# SoM.net
KiCad netlist of a schematic drawn in Altium Designer
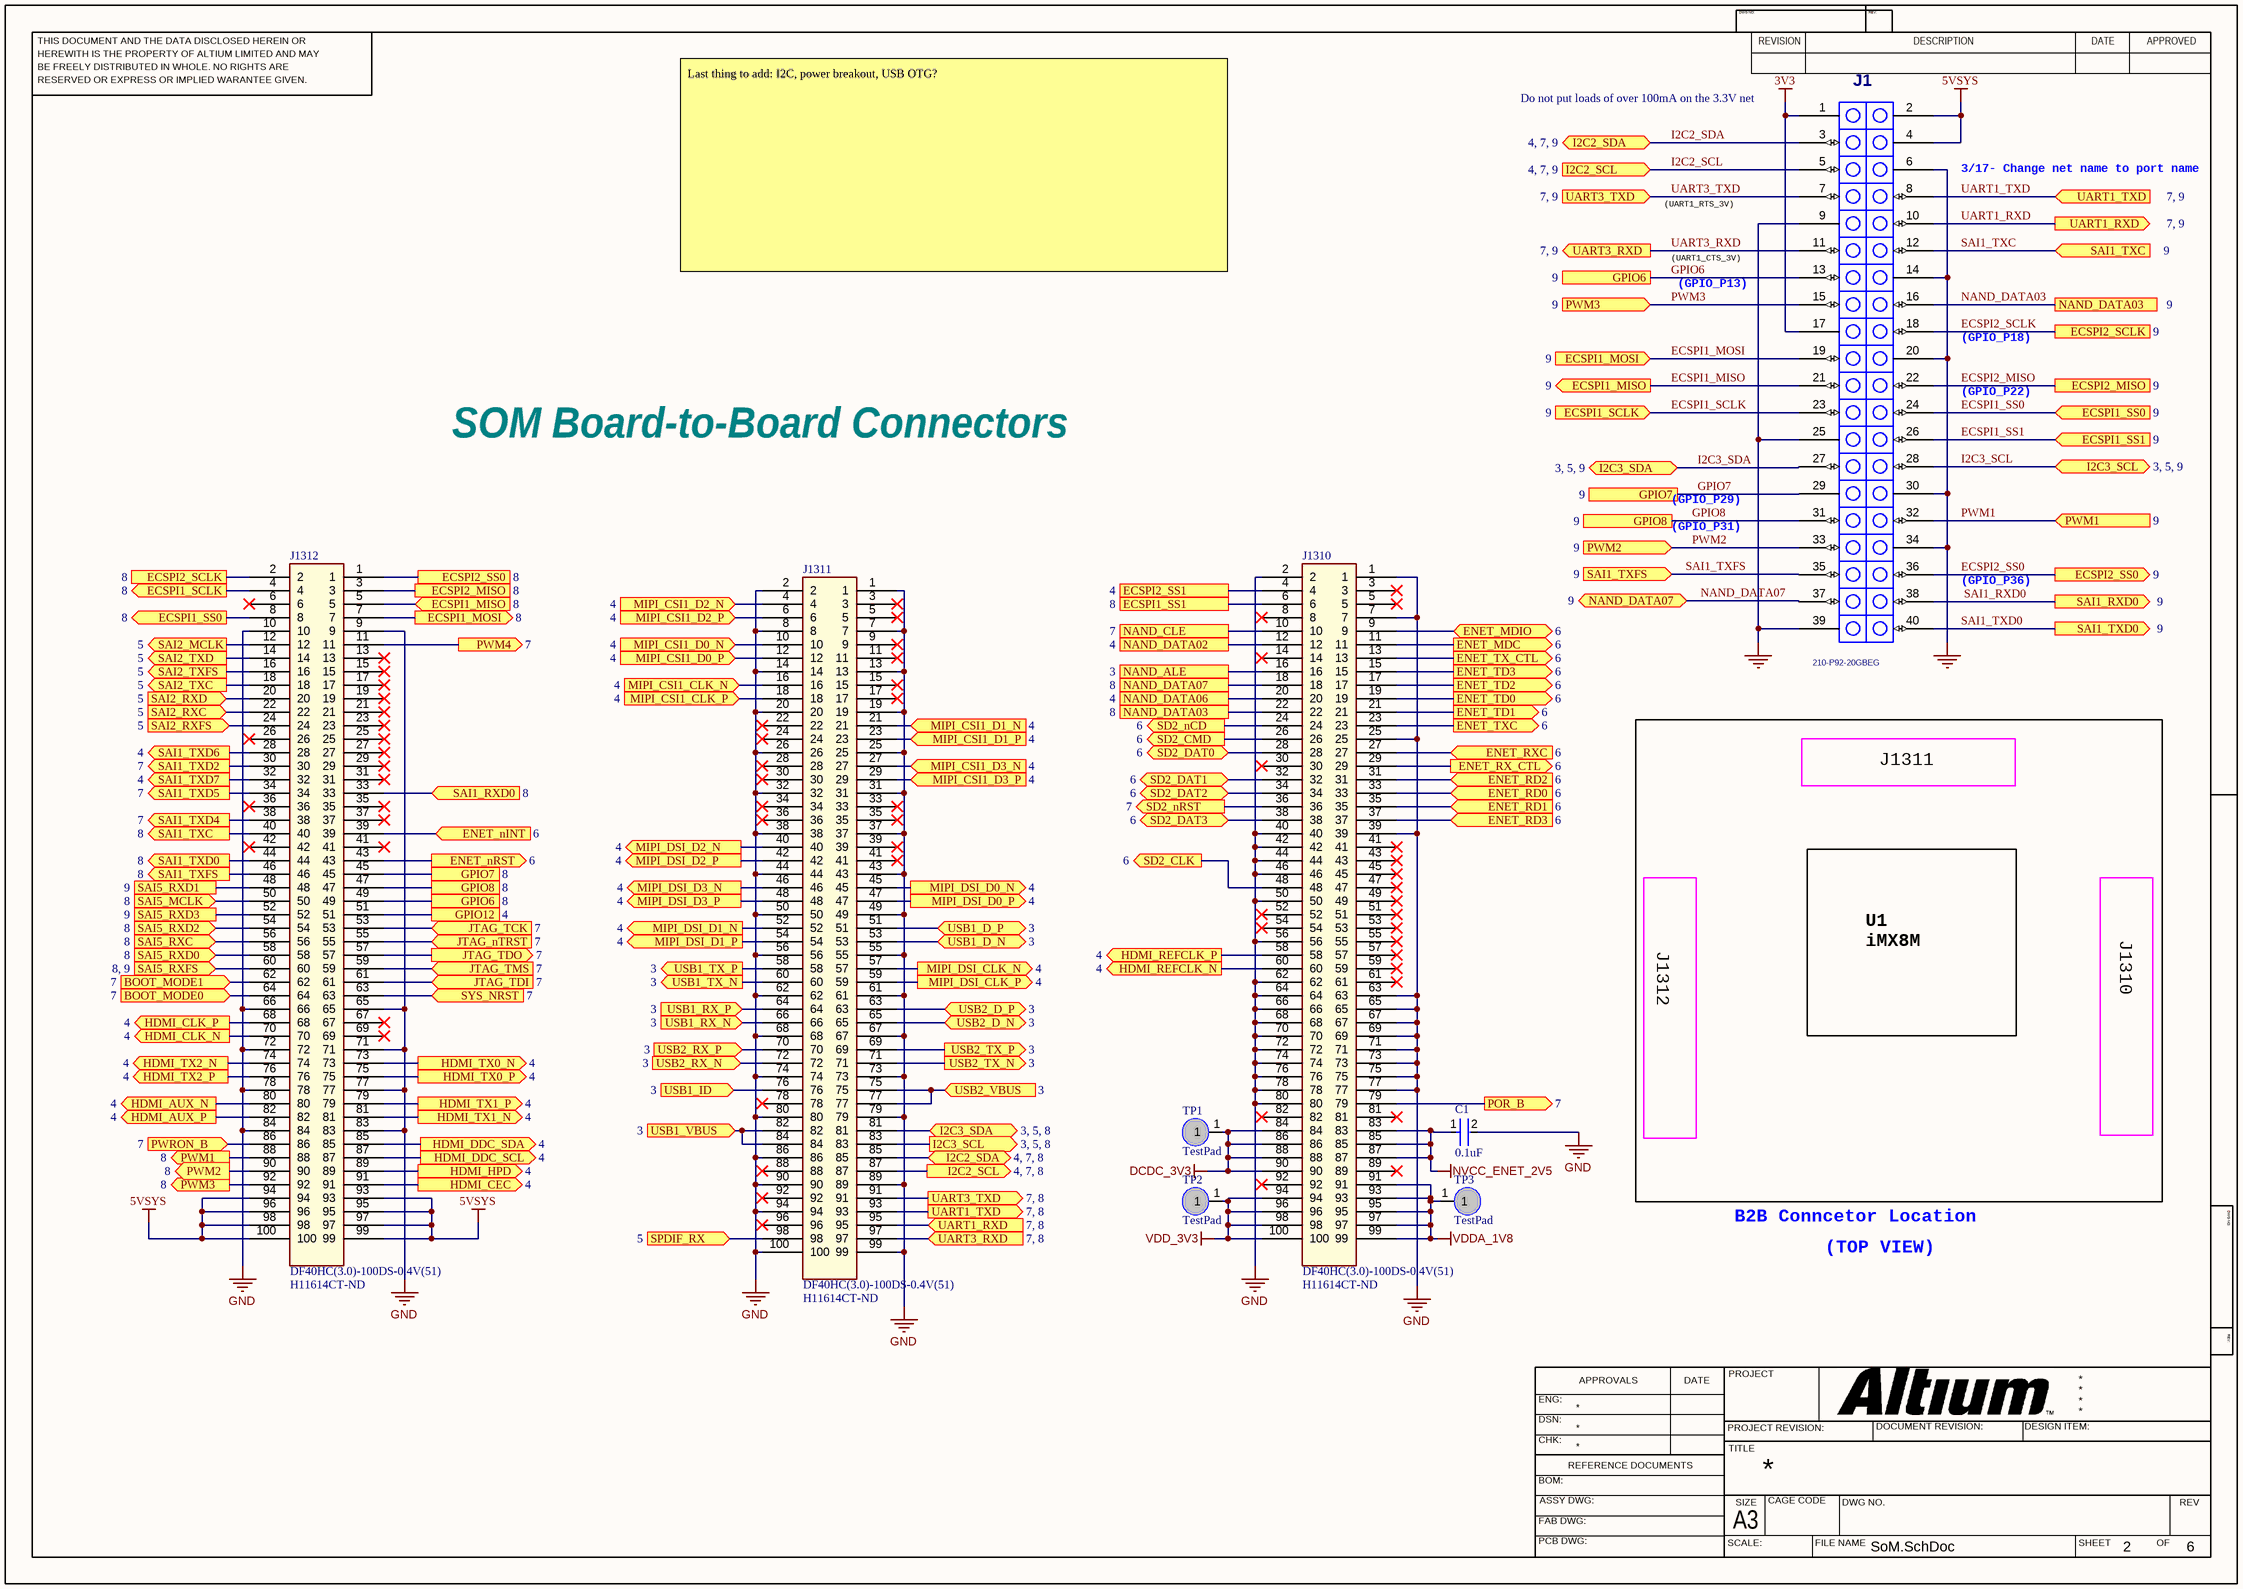
[diagram p0: SoM.SchDoc]

(export (version "E")
  (design (tool "Eeschema 10.0.6"))
  (components
    (comp (ref "C1")
      (value "0.1uF")
      (footprint "FP-C0603-CJ-MFG")
      (description "C0603X104K5RACTU CAP CER 0.1UF 50V X7R 0603")
      (fields (field (name "MANUFACTURER PART NUMBER") "C0603X104K5RACTU") (field (name "VOLTAGE") "50V"))
      (libsource (lib "Altium Content Vault") (part "11868f565c42a9108669ba33697ecf6"))
    )
    (comp (ref "J1")
      (value "210-P92-20GBEG")
      (footprint "LayoutFootprintsGoogle:2X20")
      (description "SOCKET 2X20 100-MIL STRAIGHT SMT")
      (libsource (lib "SpacePark") (part "CONN_HEADER_20x2_SMT"))
    )
    (comp (ref "J1310")
      (value "DF40HC(3.0)-100DS-0.4V(51)")
      (footprint "LayoutFootprintsGoogle:DF40HC30100DS04V51")
      (description "CONN HDR 100POS 0.4MM SMD GOLD")
      (fields (field (name "SUPPLIER PART NUMBER 1") "H11614CT-ND"))
      (libsource (lib "SpacePark") (part "CONN_HIROSE-DF40C-100DP-0.4V(51)"))
    )
    (comp (ref "J1311")
      (value "DF40HC(3.0)-100DS-0.4V(51)")
      (footprint "LayoutFootprintsGoogle:DF40HC30100DS04V51")
      (description "CONN HDR 100POS 0.4MM SMD GOLD")
      (fields (field (name "SUPPLIER PART NUMBER 1") "H11614CT-ND"))
      (libsource (lib "SpacePark") (part "CONN_HIROSE-DF40C-100DP-0.4V(51)"))
    )
    (comp (ref "J1312")
      (value "DF40HC(3.0)-100DS-0.4V(51)")
      (footprint "LayoutFootprintsGoogle:DF40HC30100DS04V51")
      (description "CONN HDR 100POS 0.4MM SMD GOLD")
      (fields (field (name "SUPPLIER PART NUMBER 1") "H11614CT-ND"))
      (libsource (lib "SpacePark") (part "CONN_HIROSE-DF40C-100DP-0.4V(51)"))
    )
    (comp (ref "TP1")
      (value "TestPad")
      (footprint "TestPad50mil")
      (libsource (lib "SchemSymbolsGoogle") (part "TestPad"))
    )
    (comp (ref "TP2")
      (value "TestPad")
      (footprint "TestPad50mil")
      (libsource (lib "SchemSymbolsGoogle") (part "TestPad"))
    )
    (comp (ref "TP3")
      (value "TestPad")
      (footprint "TestPad50mil")
      (libsource (lib "SchemSymbolsGoogle") (part "TestPad"))
    )
  )
  (nets
    (net (code "1") (name "/BOOT_MODE0") (class "Default")
      (node (ref "J1312") (pin "64") (pinfunction "64_64") (pintype "passive"))
    )
    (net (code "2") (name "/BOOT_MODE1") (class "Default")
      (node (ref "J1312") (pin "62") (pinfunction "62_62") (pintype "passive"))
    )
    (net (code "3") (name "/ECSPI1_MISO") (class "Default")
      (node (ref "J1") (pin "21") (pinfunction "21_21") (pintype "bidirectional"))
      (node (ref "J1312") (pin "5") (pinfunction "5_5") (pintype "passive"))
    )
    (net (code "4") (name "/ECSPI1_MOSI") (class "Default")
      (node (ref "J1") (pin "19") (pinfunction "19_19") (pintype "bidirectional"))
      (node (ref "J1312") (pin "7") (pinfunction "7_7") (pintype "passive"))
    )
    (net (code "5") (name "/ECSPI1_SCLK") (class "Default")
      (node (ref "J1") (pin "23") (pinfunction "23_23") (pintype "bidirectional"))
      (node (ref "J1312") (pin "4") (pinfunction "4_4") (pintype "passive"))
    )
    (net (code "6") (name "/ECSPI1_SS0") (class "Default")
      (node (ref "J1") (pin "24") (pinfunction "24_24") (pintype "bidirectional"))
      (node (ref "J1312") (pin "8") (pinfunction "8_8") (pintype "passive"))
    )
    (net (code "7") (name "/ECSPI1_SS1") (class "Default")
      (node (ref "J1") (pin "26") (pinfunction "26_26") (pintype "bidirectional"))
      (node (ref "J1310") (pin "6") (pinfunction "6_6") (pintype "passive"))
    )
    (net (code "8") (name "/ECSPI2_MISO") (class "Default")
      (node (ref "J1") (pin "22") (pinfunction "22_22") (pintype "bidirectional"))
      (node (ref "J1312") (pin "3") (pinfunction "3_3") (pintype "passive"))
    )
    (net (code "9") (name "/ECSPI2_SCLK") (class "Default")
      (node (ref "J1") (pin "18") (pinfunction "18_18") (pintype "bidirectional"))
      (node (ref "J1312") (pin "2") (pinfunction "2_2") (pintype "passive"))
    )
    (net (code "10") (name "/ECSPI2_SS0") (class "Default")
      (node (ref "J1") (pin "36") (pinfunction "36_36") (pintype "bidirectional"))
      (node (ref "J1312") (pin "1") (pinfunction "1_1") (pintype "passive"))
    )
    (net (code "11") (name "/ECSPI2_SS1") (class "Default")
      (node (ref "J1310") (pin "4") (pinfunction "4_4") (pintype "passive"))
    )
    (net (code "12") (name "/ENET_MDC") (class "Default")
      (node (ref "J1310") (pin "11") (pinfunction "11_11") (pintype "passive"))
    )
    (net (code "13") (name "/ENET_MDIO") (class "Default")
      (node (ref "J1310") (pin "9") (pinfunction "9_9") (pintype "passive"))
    )
    (net (code "14") (name "/ENET_RD0") (class "Default")
      (node (ref "J1310") (pin "33") (pinfunction "33_33") (pintype "passive"))
    )
    (net (code "15") (name "/ENET_RD1") (class "Default")
      (node (ref "J1310") (pin "35") (pinfunction "35_35") (pintype "passive"))
    )
    (net (code "16") (name "/ENET_RD2") (class "Default")
      (node (ref "J1310") (pin "31") (pinfunction "31_31") (pintype "passive"))
    )
    (net (code "17") (name "/ENET_RD3") (class "Default")
      (node (ref "J1310") (pin "37") (pinfunction "37_37") (pintype "passive"))
    )
    (net (code "18") (name "/ENET_RXC") (class "Default")
      (node (ref "J1310") (pin "27") (pinfunction "27_27") (pintype "passive"))
    )
    (net (code "19") (name "/ENET_RX_CTL") (class "Default")
      (node (ref "J1310") (pin "29") (pinfunction "29_29") (pintype "passive"))
    )
    (net (code "20") (name "/ENET_TD0") (class "Default")
      (node (ref "J1310") (pin "19") (pinfunction "19_19") (pintype "passive"))
    )
    (net (code "21") (name "/ENET_TD1") (class "Default")
      (node (ref "J1310") (pin "21") (pinfunction "21_21") (pintype "passive"))
    )
    (net (code "22") (name "/ENET_TD2") (class "Default")
      (node (ref "J1310") (pin "17") (pinfunction "17_17") (pintype "passive"))
    )
    (net (code "23") (name "/ENET_TD3") (class "Default")
      (node (ref "J1310") (pin "15") (pinfunction "15_15") (pintype "passive"))
    )
    (net (code "24") (name "/ENET_TXC") (class "Default")
      (node (ref "J1310") (pin "23") (pinfunction "23_23") (pintype "passive"))
    )
    (net (code "25") (name "/ENET_TX_CTL") (class "Default")
      (node (ref "J1310") (pin "13") (pinfunction "13_13") (pintype "passive"))
    )
    (net (code "26") (name "/ENET_nINT") (class "Default")
      (node (ref "J1312") (pin "39") (pinfunction "39_39") (pintype "passive"))
    )
    (net (code "27") (name "/ENET_nRST") (class "Default")
      (node (ref "J1312") (pin "43") (pinfunction "43_43") (pintype "passive"))
    )
    (net (code "28") (name "/GPIO6") (class "Default")
      (node (ref "J1") (pin "13") (pinfunction "13_13") (pintype "bidirectional"))
      (node (ref "J1312") (pin "49") (pinfunction "49_49") (pintype "passive"))
    )
    (net (code "29") (name "/GPIO7") (class "Default")
      (node (ref "J1") (pin "29") (pinfunction "29_29") (pintype "passive"))
      (node (ref "J1312") (pin "45") (pinfunction "45_45") (pintype "passive"))
    )
    (net (code "30") (name "/GPIO8") (class "Default")
      (node (ref "J1") (pin "31") (pinfunction "31_31") (pintype "bidirectional"))
      (node (ref "J1312") (pin "47") (pinfunction "47_47") (pintype "passive"))
    )
    (net (code "31") (name "/GPIO12") (class "Default")
      (node (ref "J1312") (pin "51") (pinfunction "51_51") (pintype "passive"))
    )
    (net (code "32") (name "/HDMI_AUX_N") (class "Default")
      (node (ref "J1312") (pin "80") (pinfunction "80_80") (pintype "passive"))
    )
    (net (code "33") (name "/HDMI_AUX_P") (class "Default")
      (node (ref "J1312") (pin "82") (pinfunction "82_82") (pintype "passive"))
    )
    (net (code "34") (name "/HDMI_CEC") (class "Default")
      (node (ref "J1312") (pin "91") (pinfunction "91_91") (pintype "passive"))
    )
    (net (code "35") (name "/HDMI_CLK_N") (class "Default")
      (node (ref "J1312") (pin "70") (pinfunction "70_70") (pintype "passive"))
    )
    (net (code "36") (name "/HDMI_CLK_P") (class "Default")
      (node (ref "J1312") (pin "68") (pinfunction "68_68") (pintype "passive"))
    )
    (net (code "37") (name "/HDMI_DDC_SCL") (class "Default")
      (node (ref "J1312") (pin "87") (pinfunction "87_87") (pintype "passive"))
    )
    (net (code "38") (name "/HDMI_DDC_SDA") (class "Default")
      (node (ref "J1312") (pin "85") (pinfunction "85_85") (pintype "passive"))
    )
    (net (code "39") (name "/HDMI_HPD") (class "Default")
      (node (ref "J1312") (pin "89") (pinfunction "89_89") (pintype "passive"))
    )
    (net (code "40") (name "/HDMI_REFCLK_N") (class "Default")
      (node (ref "J1310") (pin "60") (pinfunction "60_60") (pintype "passive"))
    )
    (net (code "41") (name "/HDMI_REFCLK_P") (class "Default")
      (node (ref "J1310") (pin "58") (pinfunction "58_58") (pintype "passive"))
    )
    (net (code "42") (name "/HDMI_TX0_N") (class "Default")
      (node (ref "J1312") (pin "73") (pinfunction "73_73") (pintype "passive"))
    )
    (net (code "43") (name "/HDMI_TX0_P") (class "Default")
      (node (ref "J1312") (pin "75") (pinfunction "75_75") (pintype "passive"))
    )
    (net (code "44") (name "/HDMI_TX1_N") (class "Default")
      (node (ref "J1312") (pin "81") (pinfunction "81_81") (pintype "passive"))
    )
    (net (code "45") (name "/HDMI_TX1_P") (class "Default")
      (node (ref "J1312") (pin "79") (pinfunction "79_79") (pintype "passive"))
    )
    (net (code "46") (name "/HDMI_TX2_N") (class "Default")
      (node (ref "J1312") (pin "74") (pinfunction "74_74") (pintype "passive"))
    )
    (net (code "47") (name "/HDMI_TX2_P") (class "Default")
      (node (ref "J1312") (pin "76") (pinfunction "76_76") (pintype "passive"))
    )
    (net (code "48") (name "/I2C2_SCL") (class "Default")
      (node (ref "J1") (pin "5") (pinfunction "5_5") (pintype "bidirectional"))
      (node (ref "J1311") (pin "87") (pinfunction "87_87") (pintype "passive"))
    )
    (net (code "49") (name "/I2C2_SDA") (class "Default")
      (node (ref "J1") (pin "3") (pinfunction "3_3") (pintype "bidirectional"))
      (node (ref "J1311") (pin "85") (pinfunction "85_85") (pintype "passive"))
    )
    (net (code "50") (name "/I2C3_SCL") (class "Default")
      (node (ref "J1") (pin "28") (pinfunction "28_28") (pintype "bidirectional"))
      (node (ref "J1311") (pin "83") (pinfunction "83_83") (pintype "passive"))
    )
    (net (code "51") (name "/I2C3_SDA") (class "Default")
      (node (ref "J1") (pin "27") (pinfunction "27_27") (pintype "bidirectional"))
      (node (ref "J1311") (pin "81") (pinfunction "81_81") (pintype "passive"))
    )
    (net (code "52") (name "/JTAG_TCK") (class "Default")
      (node (ref "J1312") (pin "53") (pinfunction "53_53") (pintype "passive"))
    )
    (net (code "53") (name "/JTAG_TDI") (class "Default")
      (node (ref "J1312") (pin "61") (pinfunction "61_61") (pintype "passive"))
    )
    (net (code "54") (name "/JTAG_TDO") (class "Default")
      (node (ref "J1312") (pin "57") (pinfunction "57_57") (pintype "passive"))
    )
    (net (code "55") (name "/JTAG_TMS") (class "Default")
      (node (ref "J1312") (pin "59") (pinfunction "59_59") (pintype "passive"))
    )
    (net (code "56") (name "/JTAG_nTRST") (class "Default")
      (node (ref "J1312") (pin "55") (pinfunction "55_55") (pintype "passive"))
    )
    (net (code "57") (name "/MIPI_CSI1_CLK_N") (class "Default")
      (node (ref "J1311") (pin "16") (pinfunction "16_16") (pintype "passive"))
    )
    (net (code "58") (name "/MIPI_CSI1_CLK_P") (class "Default")
      (node (ref "J1311") (pin "18") (pinfunction "18_18") (pintype "passive"))
    )
    (net (code "59") (name "/MIPI_CSI1_D0_N") (class "Default")
      (node (ref "J1311") (pin "10") (pinfunction "10_10") (pintype "passive"))
    )
    (net (code "60") (name "/MIPI_CSI1_D0_P") (class "Default")
      (node (ref "J1311") (pin "12") (pinfunction "12_12") (pintype "passive"))
    )
    (net (code "61") (name "/MIPI_CSI1_D1_N") (class "Default")
      (node (ref "J1311") (pin "21") (pinfunction "21_21") (pintype "passive"))
    )
    (net (code "62") (name "/MIPI_CSI1_D1_P") (class "Default")
      (node (ref "J1311") (pin "23") (pinfunction "23_23") (pintype "passive"))
    )
    (net (code "63") (name "/MIPI_CSI1_D2_N") (class "Default")
      (node (ref "J1311") (pin "4") (pinfunction "4_4") (pintype "passive"))
    )
    (net (code "64") (name "/MIPI_CSI1_D2_P") (class "Default")
      (node (ref "J1311") (pin "6") (pinfunction "6_6") (pintype "passive"))
    )
    (net (code "65") (name "/MIPI_CSI1_D3_N") (class "Default")
      (node (ref "J1311") (pin "27") (pinfunction "27_27") (pintype "passive"))
    )
    (net (code "66") (name "/MIPI_CSI1_D3_P") (class "Default")
      (node (ref "J1311") (pin "29") (pinfunction "29_29") (pintype "passive"))
    )
    (net (code "67") (name "/MIPI_DSI_CLK_N") (class "Default")
      (node (ref "J1311") (pin "57") (pinfunction "57_57") (pintype "passive"))
    )
    (net (code "68") (name "/MIPI_DSI_CLK_P") (class "Default")
      (node (ref "J1311") (pin "59") (pinfunction "59_59") (pintype "passive"))
    )
    (net (code "69") (name "/MIPI_DSI_D0_N") (class "Default")
      (node (ref "J1311") (pin "45") (pinfunction "45_45") (pintype "passive"))
    )
    (net (code "70") (name "/MIPI_DSI_D0_P") (class "Default")
      (node (ref "J1311") (pin "47") (pinfunction "47_47") (pintype "passive"))
    )
    (net (code "71") (name "/MIPI_DSI_D1_N") (class "Default")
      (node (ref "J1311") (pin "52") (pinfunction "52_52") (pintype "passive"))
    )
    (net (code "72") (name "/MIPI_DSI_D1_P") (class "Default")
      (node (ref "J1311") (pin "54") (pinfunction "54_54") (pintype "passive"))
    )
    (net (code "73") (name "/MIPI_DSI_D2_N") (class "Default")
      (node (ref "J1311") (pin "40") (pinfunction "40_40") (pintype "passive"))
    )
    (net (code "74") (name "/MIPI_DSI_D2_P") (class "Default")
      (node (ref "J1311") (pin "42") (pinfunction "42_42") (pintype "passive"))
    )
    (net (code "75") (name "/MIPI_DSI_D3_N") (class "Default")
      (node (ref "J1311") (pin "46") (pinfunction "46_46") (pintype "passive"))
    )
    (net (code "76") (name "/MIPI_DSI_D3_P") (class "Default")
      (node (ref "J1311") (pin "48") (pinfunction "48_48") (pintype "passive"))
    )
    (net (code "77") (name "/NAND_ALE") (class "Default")
      (node (ref "J1310") (pin "16") (pinfunction "16_16") (pintype "passive"))
    )
    (net (code "78") (name "/NAND_CLE") (class "Default")
      (node (ref "J1310") (pin "10") (pinfunction "10_10") (pintype "passive"))
    )
    (net (code "79") (name "/NAND_DATA02") (class "Default")
      (node (ref "J1310") (pin "12") (pinfunction "12_12") (pintype "passive"))
    )
    (net (code "80") (name "/NAND_DATA03") (class "Default")
      (node (ref "J1") (pin "16") (pinfunction "16_16") (pintype "bidirectional"))
      (node (ref "J1310") (pin "22") (pinfunction "22_22") (pintype "passive"))
    )
    (net (code "81") (name "/NAND_DATA06") (class "Default")
      (node (ref "J1310") (pin "20") (pinfunction "20_20") (pintype "passive"))
    )
    (net (code "82") (name "/NAND_DATA07") (class "Default")
      (node (ref "J1") (pin "37") (pinfunction "37_37") (pintype "bidirectional"))
      (node (ref "J1310") (pin "18") (pinfunction "18_18") (pintype "passive"))
    )
    (net (code "83") (name "/POR_B") (class "Default")
      (node (ref "J1310") (pin "79") (pinfunction "79_79") (pintype "passive"))
    )
    (net (code "84") (name "/PWM1") (class "Default")
      (node (ref "J1") (pin "32") (pinfunction "32_32") (pintype "bidirectional"))
      (node (ref "J1312") (pin "88") (pinfunction "88_88") (pintype "passive"))
    )
    (net (code "85") (name "/PWM2") (class "Default")
      (node (ref "J1") (pin "33") (pinfunction "33_33") (pintype "bidirectional"))
      (node (ref "J1312") (pin "90") (pinfunction "90_90") (pintype "passive"))
    )
    (net (code "86") (name "/PWM3") (class "Default")
      (node (ref "J1") (pin "15") (pinfunction "15_15") (pintype "bidirectional"))
      (node (ref "J1312") (pin "92") (pinfunction "92_92") (pintype "passive"))
    )
    (net (code "87") (name "/PWM4") (class "Default")
      (node (ref "J1312") (pin "11") (pinfunction "11_11") (pintype "passive"))
    )
    (net (code "88") (name "/PWRON_B") (class "Default")
      (node (ref "J1312") (pin "86") (pinfunction "86_86") (pintype "passive"))
    )
    (net (code "89") (name "/SAI1_RXD0") (class "Default")
      (node (ref "J1") (pin "38") (pinfunction "38_38") (pintype "bidirectional"))
      (node (ref "J1312") (pin "33") (pinfunction "33_33") (pintype "passive"))
    )
    (net (code "90") (name "/SAI1_TXC") (class "Default")
      (node (ref "J1") (pin "12") (pinfunction "12_12") (pintype "bidirectional"))
      (node (ref "J1312") (pin "40") (pinfunction "40_40") (pintype "passive"))
    )
    (net (code "91") (name "/SAI1_TXD0") (class "Default")
      (node (ref "J1") (pin "40") (pinfunction "40_40") (pintype "bidirectional"))
      (node (ref "J1312") (pin "44") (pinfunction "44_44") (pintype "passive"))
    )
    (net (code "92") (name "/SAI1_TXD2") (class "Default")
      (node (ref "J1312") (pin "30") (pinfunction "30_30") (pintype "passive"))
    )
    (net (code "93") (name "/SAI1_TXD4") (class "Default")
      (node (ref "J1312") (pin "38") (pinfunction "38_38") (pintype "passive"))
    )
    (net (code "94") (name "/SAI1_TXD5") (class "Default")
      (node (ref "J1312") (pin "34") (pinfunction "34_34") (pintype "passive"))
    )
    (net (code "95") (name "/SAI1_TXD6") (class "Default")
      (node (ref "J1312") (pin "28") (pinfunction "28_28") (pintype "passive"))
    )
    (net (code "96") (name "/SAI1_TXD7") (class "Default")
      (node (ref "J1312") (pin "32") (pinfunction "32_32") (pintype "passive"))
    )
    (net (code "97") (name "/SAI1_TXFS") (class "Default")
      (node (ref "J1") (pin "35") (pinfunction "35_35") (pintype "bidirectional"))
      (node (ref "J1312") (pin "46") (pinfunction "46_46") (pintype "passive"))
    )
    (net (code "98") (name "/SAI2_MCLK") (class "Default")
      (node (ref "J1312") (pin "12") (pinfunction "12_12") (pintype "passive"))
    )
    (net (code "99") (name "/SAI2_RXC") (class "Default")
      (node (ref "J1312") (pin "22") (pinfunction "22_22") (pintype "passive"))
    )
    (net (code "100") (name "/SAI2_RXD") (class "Default")
      (node (ref "J1312") (pin "20") (pinfunction "20_20") (pintype "passive"))
    )
    (net (code "101") (name "/SAI2_RXFS") (class "Default")
      (node (ref "J1312") (pin "24") (pinfunction "24_24") (pintype "passive"))
    )
    (net (code "102") (name "/SAI2_TXC") (class "Default")
      (node (ref "J1312") (pin "18") (pinfunction "18_18") (pintype "passive"))
    )
    (net (code "103") (name "/SAI2_TXD") (class "Default")
      (node (ref "J1312") (pin "14") (pinfunction "14_14") (pintype "passive"))
    )
    (net (code "104") (name "/SAI2_TXFS") (class "Default")
      (node (ref "J1312") (pin "16") (pinfunction "16_16") (pintype "passive"))
    )
    (net (code "105") (name "/SAI5_MCLK") (class "Default")
      (node (ref "J1312") (pin "50") (pinfunction "50_50") (pintype "passive"))
    )
    (net (code "106") (name "/SAI5_RXC") (class "Default")
      (node (ref "J1312") (pin "56") (pinfunction "56_56") (pintype "passive"))
    )
    (net (code "107") (name "/SAI5_RXD0") (class "Default")
      (node (ref "J1312") (pin "58") (pinfunction "58_58") (pintype "passive"))
    )
    (net (code "108") (name "/SAI5_RXD1") (class "Default")
      (node (ref "J1312") (pin "48") (pinfunction "48_48") (pintype "passive"))
    )
    (net (code "109") (name "/SAI5_RXD2") (class "Default")
      (node (ref "J1312") (pin "54") (pinfunction "54_54") (pintype "passive"))
    )
    (net (code "110") (name "/SAI5_RXD3") (class "Default")
      (node (ref "J1312") (pin "52") (pinfunction "52_52") (pintype "passive"))
    )
    (net (code "111") (name "/SAI5_RXFS") (class "Default")
      (node (ref "J1312") (pin "60") (pinfunction "60_60") (pintype "passive"))
    )
    (net (code "112") (name "/SD2_CLK") (class "Default")
      (node (ref "J1310") (pin "48") (pinfunction "48_48") (pintype "passive"))
    )
    (net (code "113") (name "/SD2_CMD") (class "Default")
      (node (ref "J1310") (pin "26") (pinfunction "26_26") (pintype "passive"))
    )
    (net (code "114") (name "/SD2_DAT0") (class "Default")
      (node (ref "J1310") (pin "28") (pinfunction "28_28") (pintype "passive"))
    )
    (net (code "115") (name "/SD2_DAT1") (class "Default")
      (node (ref "J1310") (pin "32") (pinfunction "32_32") (pintype "passive"))
    )
    (net (code "116") (name "/SD2_DAT2") (class "Default")
      (node (ref "J1310") (pin "34") (pinfunction "34_34") (pintype "passive"))
    )
    (net (code "117") (name "/SD2_DAT3") (class "Default")
      (node (ref "J1310") (pin "38") (pinfunction "38_38") (pintype "passive"))
    )
    (net (code "118") (name "/SD2_nCD") (class "Default")
      (node (ref "J1310") (pin "24") (pinfunction "24_24") (pintype "passive"))
    )
    (net (code "119") (name "/SD2_nRST") (class "Default")
      (node (ref "J1310") (pin "36") (pinfunction "36_36") (pintype "passive"))
    )
    (net (code "120") (name "/SPDIF_RX") (class "Default")
      (node (ref "J1311") (pin "98") (pinfunction "98_98") (pintype "passive"))
    )
    (net (code "121") (name "/SYS_NRST") (class "Default")
      (node (ref "J1312") (pin "63") (pinfunction "63_63") (pintype "passive"))
    )
    (net (code "122") (name "/UART1_RXD") (class "Default")
      (node (ref "J1") (pin "10") (pinfunction "10_10") (pintype "bidirectional"))
      (node (ref "J1311") (pin "95") (pinfunction "95_95") (pintype "passive"))
    )
    (net (code "123") (name "/UART1_TXD") (class "Default")
      (node (ref "J1") (pin "8") (pinfunction "8_8") (pintype "bidirectional"))
      (node (ref "J1311") (pin "93") (pinfunction "93_93") (pintype "passive"))
    )
    (net (code "124") (name "/UART3_RXD") (class "Default")
      (node (ref "J1") (pin "11") (pinfunction "11_11") (pintype "bidirectional"))
      (node (ref "J1311") (pin "97") (pinfunction "97_97") (pintype "passive"))
    )
    (net (code "125") (name "/UART3_TXD") (class "Default")
      (node (ref "J1") (pin "7") (pinfunction "7_7") (pintype "bidirectional"))
      (node (ref "J1311") (pin "91") (pinfunction "91_91") (pintype "passive"))
    )
    (net (code "126") (name "/USB1_D_N") (class "Default")
      (node (ref "J1311") (pin "53") (pinfunction "53_53") (pintype "passive"))
    )
    (net (code "127") (name "/USB1_D_P") (class "Default")
      (node (ref "J1311") (pin "51") (pinfunction "51_51") (pintype "passive"))
    )
    (net (code "128") (name "/USB1_ID") (class "Default")
      (node (ref "J1311") (pin "76") (pinfunction "76_76") (pintype "passive"))
    )
    (net (code "129") (name "/USB1_RX_N") (class "Default")
      (node (ref "J1311") (pin "66") (pinfunction "66_66") (pintype "passive"))
    )
    (net (code "130") (name "/USB1_RX_P") (class "Default")
      (node (ref "J1311") (pin "64") (pinfunction "64_64") (pintype "passive"))
    )
    (net (code "131") (name "/USB1_TX_N") (class "Default")
      (node (ref "J1311") (pin "60") (pinfunction "60_60") (pintype "passive"))
    )
    (net (code "132") (name "/USB1_TX_P") (class "Default")
      (node (ref "J1311") (pin "58") (pinfunction "58_58") (pintype "passive"))
    )
    (net (code "133") (name "/USB1_VBUS") (class "Default")
      (node (ref "J1311") (pin "82") (pinfunction "82_82") (pintype "passive"))
      (node (ref "J1311") (pin "84") (pinfunction "84_84") (pintype "passive"))
    )
    (net (code "134") (name "/USB2_D_N") (class "Default")
      (node (ref "J1311") (pin "65") (pinfunction "65_65") (pintype "passive"))
    )
    (net (code "135") (name "/USB2_D_P") (class "Default")
      (node (ref "J1311") (pin "63") (pinfunction "63_63") (pintype "passive"))
    )
    (net (code "136") (name "/USB2_RX_N") (class "Default")
      (node (ref "J1311") (pin "72") (pinfunction "72_72") (pintype "passive"))
    )
    (net (code "137") (name "/USB2_RX_P") (class "Default")
      (node (ref "J1311") (pin "70") (pinfunction "70_70") (pintype "passive"))
    )
    (net (code "138") (name "/USB2_TX_N") (class "Default")
      (node (ref "J1311") (pin "71") (pinfunction "71_71") (pintype "passive"))
    )
    (net (code "139") (name "/USB2_TX_P") (class "Default")
      (node (ref "J1311") (pin "69") (pinfunction "69_69") (pintype "passive"))
    )
    (net (code "140") (name "/USB2_VBUS") (class "Default")
      (node (ref "J1311") (pin "75") (pinfunction "75_75") (pintype "passive"))
      (node (ref "J1311") (pin "77") (pinfunction "77_77") (pintype "passive"))
    )
    (net (code "141") (name "3V3") (class "Default")
      (node (ref "J1") (pin "1") (pinfunction "1_1") (pintype "passive"))
      (node (ref "J1") (pin "17") (pinfunction "17_17") (pintype "passive"))
    )
    (net (code "142") (name "5VSYS") (class "Default")
      (node (ref "J1") (pin "2") (pinfunction "2_2") (pintype "passive"))
      (node (ref "J1") (pin "4") (pinfunction "4_4") (pintype "passive"))
      (node (ref "J1312") (pin "100") (pinfunction "100_100") (pintype "passive"))
      (node (ref "J1312") (pin "93") (pinfunction "93_93") (pintype "passive"))
      (node (ref "J1312") (pin "94") (pinfunction "94_94") (pintype "passive"))
      (node (ref "J1312") (pin "95") (pinfunction "95_95") (pintype "passive"))
      (node (ref "J1312") (pin "96") (pinfunction "96_96") (pintype "passive"))
      (node (ref "J1312") (pin "97") (pinfunction "97_97") (pintype "passive"))
      (node (ref "J1312") (pin "98") (pinfunction "98_98") (pintype "passive"))
      (node (ref "J1312") (pin "99") (pinfunction "99_99") (pintype "passive"))
    )
    (net (code "143") (name "DCDC_3V3") (class "Default")
      (node (ref "J1310") (pin "84") (pinfunction "84_84") (pintype "passive"))
      (node (ref "J1310") (pin "86") (pinfunction "86_86") (pintype "passive"))
      (node (ref "J1310") (pin "88") (pinfunction "88_88") (pintype "passive"))
      (node (ref "J1310") (pin "90") (pinfunction "90_90") (pintype "passive"))
      (node (ref "TP1") (pin "1") (pinfunction "1_1") (pintype "passive"))
    )
    (net (code "144") (name "GND") (class "Default")
      (node (ref "C1") (pin "2") (pinfunction "2_2") (pintype "passive"))
      (node (ref "J1") (pin "14") (pinfunction "14_14") (pintype "passive"))
      (node (ref "J1") (pin "20") (pinfunction "20_20") (pintype "passive"))
      (node (ref "J1") (pin "25") (pinfunction "25_25") (pintype "passive"))
      (node (ref "J1") (pin "30") (pinfunction "30_30") (pintype "passive"))
      (node (ref "J1") (pin "34") (pinfunction "34_34") (pintype "passive"))
      (node (ref "J1") (pin "39") (pinfunction "39_39") (pintype "passive"))
      (node (ref "J1") (pin "6") (pinfunction "6_6") (pintype "passive"))
      (node (ref "J1") (pin "9") (pinfunction "9_9") (pintype "passive"))
      (node (ref "J1310") (pin "1") (pinfunction "1_1") (pintype "passive"))
      (node (ref "J1310") (pin "2") (pinfunction "2_2") (pintype "passive"))
      (node (ref "J1310") (pin "25") (pinfunction "25_25") (pintype "passive"))
      (node (ref "J1310") (pin "39") (pinfunction "39_39") (pintype "passive"))
      (node (ref "J1310") (pin "40") (pinfunction "40_40") (pintype "passive"))
      (node (ref "J1310") (pin "42") (pinfunction "42_42") (pintype "passive"))
      (node (ref "J1310") (pin "44") (pinfunction "44_44") (pintype "passive"))
      (node (ref "J1310") (pin "46") (pinfunction "46_46") (pintype "passive"))
      (node (ref "J1310") (pin "50") (pinfunction "50_50") (pintype "passive"))
      (node (ref "J1310") (pin "56") (pinfunction "56_56") (pintype "passive"))
      (node (ref "J1310") (pin "62") (pinfunction "62_62") (pintype "passive"))
      (node (ref "J1310") (pin "63") (pinfunction "63_63") (pintype "passive"))
      (node (ref "J1310") (pin "64") (pinfunction "64_64") (pintype "passive"))
      (node (ref "J1310") (pin "65") (pinfunction "65_65") (pintype "passive"))
      (node (ref "J1310") (pin "66") (pinfunction "66_66") (pintype "passive"))
      (node (ref "J1310") (pin "67") (pinfunction "67_67") (pintype "passive"))
      (node (ref "J1310") (pin "68") (pinfunction "68_68") (pintype "passive"))
      (node (ref "J1310") (pin "69") (pinfunction "69_69") (pintype "passive"))
      (node (ref "J1310") (pin "7") (pinfunction "7_7") (pintype "passive"))
      (node (ref "J1310") (pin "70") (pinfunction "70_70") (pintype "passive"))
      (node (ref "J1310") (pin "71") (pinfunction "71_71") (pintype "passive"))
      (node (ref "J1310") (pin "72") (pinfunction "72_72") (pintype "passive"))
      (node (ref "J1310") (pin "73") (pinfunction "73_73") (pintype "passive"))
      (node (ref "J1310") (pin "74") (pinfunction "74_74") (pintype "passive"))
      (node (ref "J1310") (pin "75") (pinfunction "75_75") (pintype "passive"))
      (node (ref "J1310") (pin "76") (pinfunction "76_76") (pintype "passive"))
      (node (ref "J1310") (pin "77") (pinfunction "77_77") (pintype "passive"))
      (node (ref "J1310") (pin "78") (pinfunction "78_78") (pintype "passive"))
      (node (ref "J1310") (pin "80") (pinfunction "80_80") (pintype "passive"))
      (node (ref "J1311") (pin "1") (pinfunction "1_1") (pintype "passive"))
      (node (ref "J1311") (pin "100") (pinfunction "100_100") (pintype "passive"))
      (node (ref "J1311") (pin "13") (pinfunction "13_13") (pintype "passive"))
      (node (ref "J1311") (pin "14") (pinfunction "14_14") (pintype "passive"))
      (node (ref "J1311") (pin "19") (pinfunction "19_19") (pintype "passive"))
      (node (ref "J1311") (pin "2") (pinfunction "2_2") (pintype "passive"))
      (node (ref "J1311") (pin "20") (pinfunction "20_20") (pintype "passive"))
      (node (ref "J1311") (pin "25") (pinfunction "25_25") (pintype "passive"))
      (node (ref "J1311") (pin "26") (pinfunction "26_26") (pintype "passive"))
      (node (ref "J1311") (pin "31") (pinfunction "31_31") (pintype "passive"))
      (node (ref "J1311") (pin "32") (pinfunction "32_32") (pintype "passive"))
      (node (ref "J1311") (pin "37") (pinfunction "37_37") (pintype "passive"))
      (node (ref "J1311") (pin "38") (pinfunction "38_38") (pintype "passive"))
      (node (ref "J1311") (pin "43") (pinfunction "43_43") (pintype "passive"))
      (node (ref "J1311") (pin "44") (pinfunction "44_44") (pintype "passive"))
      (node (ref "J1311") (pin "49") (pinfunction "49_49") (pintype "passive"))
      (node (ref "J1311") (pin "50") (pinfunction "50_50") (pintype "passive"))
      (node (ref "J1311") (pin "55") (pinfunction "55_55") (pintype "passive"))
      (node (ref "J1311") (pin "56") (pinfunction "56_56") (pintype "passive"))
      (node (ref "J1311") (pin "61") (pinfunction "61_61") (pintype "passive"))
      (node (ref "J1311") (pin "62") (pinfunction "62_62") (pintype "passive"))
      (node (ref "J1311") (pin "67") (pinfunction "67_67") (pintype "passive"))
      (node (ref "J1311") (pin "68") (pinfunction "68_68") (pintype "passive"))
      (node (ref "J1311") (pin "7") (pinfunction "7_7") (pintype "passive"))
      (node (ref "J1311") (pin "73") (pinfunction "73_73") (pintype "passive"))
      (node (ref "J1311") (pin "74") (pinfunction "74_74") (pintype "passive"))
      (node (ref "J1311") (pin "79") (pinfunction "79_79") (pintype "passive"))
      (node (ref "J1311") (pin "8") (pinfunction "8_8") (pintype "passive"))
      (node (ref "J1311") (pin "80") (pinfunction "80_80") (pintype "passive"))
      (node (ref "J1311") (pin "86") (pinfunction "86_86") (pintype "passive"))
      (node (ref "J1311") (pin "89") (pinfunction "89_89") (pintype "passive"))
      (node (ref "J1311") (pin "90") (pinfunction "90_90") (pintype "passive"))
      (node (ref "J1311") (pin "94") (pinfunction "94_94") (pintype "passive"))
      (node (ref "J1311") (pin "99") (pinfunction "99_99") (pintype "passive"))
      (node (ref "J1312") (pin "10") (pinfunction "10_10") (pintype "passive"))
      (node (ref "J1312") (pin "65") (pinfunction "65_65") (pintype "passive"))
      (node (ref "J1312") (pin "66") (pinfunction "66_66") (pintype "passive"))
      (node (ref "J1312") (pin "71") (pinfunction "71_71") (pintype "passive"))
      (node (ref "J1312") (pin "72") (pinfunction "72_72") (pintype "passive"))
      (node (ref "J1312") (pin "77") (pinfunction "77_77") (pintype "passive"))
      (node (ref "J1312") (pin "78") (pinfunction "78_78") (pintype "passive"))
      (node (ref "J1312") (pin "83") (pinfunction "83_83") (pintype "passive"))
      (node (ref "J1312") (pin "84") (pinfunction "84_84") (pintype "passive"))
      (node (ref "J1312") (pin "9") (pinfunction "9_9") (pintype "passive"))
    )
    (net (code "145") (name "NVCC_ENET_2V5") (class "Default")
      (node (ref "C1") (pin "1") (pinfunction "1_1") (pintype "passive"))
      (node (ref "J1310") (pin "83") (pinfunction "83_83") (pintype "passive"))
      (node (ref "J1310") (pin "85") (pinfunction "85_85") (pintype "passive"))
      (node (ref "J1310") (pin "87") (pinfunction "87_87") (pintype "passive"))
    )
    (net (code "146") (name "VDDA_1V8") (class "Default")
      (node (ref "J1310") (pin "91") (pinfunction "91_91") (pintype "passive"))
      (node (ref "J1310") (pin "93") (pinfunction "93_93") (pintype "passive"))
      (node (ref "J1310") (pin "95") (pinfunction "95_95") (pintype "passive"))
      (node (ref "J1310") (pin "97") (pinfunction "97_97") (pintype "passive"))
      (node (ref "J1310") (pin "99") (pinfunction "99_99") (pintype "passive"))
      (node (ref "TP3") (pin "1") (pinfunction "1_1") (pintype "passive"))
    )
    (net (code "147") (name "VDD_3V3") (class "Default")
      (node (ref "J1310") (pin "100") (pinfunction "100_100") (pintype "passive"))
      (node (ref "J1310") (pin "94") (pinfunction "94_94") (pintype "passive"))
      (node (ref "J1310") (pin "96") (pinfunction "96_96") (pintype "passive"))
      (node (ref "J1310") (pin "98") (pinfunction "98_98") (pintype "passive"))
      (node (ref "TP2") (pin "1") (pinfunction "1_1") (pintype "passive"))
    )
    (net (code "148") (name "unconnected-(J1310-Pad3)") (class "Default")
      (node (ref "J1310") (pin "3") (pinfunction "3_3") (pintype "passive+no_connect"))
    )
    (net (code "149") (name "unconnected-(J1310-Pad5)") (class "Default")
      (node (ref "J1310") (pin "5") (pinfunction "5_5") (pintype "passive+no_connect"))
    )
    (net (code "150") (name "unconnected-(J1310-Pad8)") (class "Default")
      (node (ref "J1310") (pin "8") (pinfunction "8_8") (pintype "passive+no_connect"))
    )
    (net (code "151") (name "unconnected-(J1310-Pad14)") (class "Default")
      (node (ref "J1310") (pin "14") (pinfunction "14_14") (pintype "passive+no_connect"))
    )
    (net (code "152") (name "unconnected-(J1310-Pad30)") (class "Default")
      (node (ref "J1310") (pin "30") (pinfunction "30_30") (pintype "passive+no_connect"))
    )
    (net (code "153") (name "unconnected-(J1310-Pad41)") (class "Default")
      (node (ref "J1310") (pin "41") (pinfunction "41_41") (pintype "passive+no_connect"))
    )
    (net (code "154") (name "unconnected-(J1310-Pad43)") (class "Default")
      (node (ref "J1310") (pin "43") (pinfunction "43_43") (pintype "passive+no_connect"))
    )
    (net (code "155") (name "unconnected-(J1310-Pad45)") (class "Default")
      (node (ref "J1310") (pin "45") (pinfunction "45_45") (pintype "passive+no_connect"))
    )
    (net (code "156") (name "unconnected-(J1310-Pad47)") (class "Default")
      (node (ref "J1310") (pin "47") (pinfunction "47_47") (pintype "passive+no_connect"))
    )
    (net (code "157") (name "unconnected-(J1310-Pad49)") (class "Default")
      (node (ref "J1310") (pin "49") (pinfunction "49_49") (pintype "passive+no_connect"))
    )
    (net (code "158") (name "unconnected-(J1310-Pad51)") (class "Default")
      (node (ref "J1310") (pin "51") (pinfunction "51_51") (pintype "passive+no_connect"))
    )
    (net (code "159") (name "unconnected-(J1310-Pad52)") (class "Default")
      (node (ref "J1310") (pin "52") (pinfunction "52_52") (pintype "passive+no_connect"))
    )
    (net (code "160") (name "unconnected-(J1310-Pad53)") (class "Default")
      (node (ref "J1310") (pin "53") (pinfunction "53_53") (pintype "passive+no_connect"))
    )
    (net (code "161") (name "unconnected-(J1310-Pad54)") (class "Default")
      (node (ref "J1310") (pin "54") (pinfunction "54_54") (pintype "passive+no_connect"))
    )
    (net (code "162") (name "unconnected-(J1310-Pad55)") (class "Default")
      (node (ref "J1310") (pin "55") (pinfunction "55_55") (pintype "passive+no_connect"))
    )
    (net (code "163") (name "unconnected-(J1310-Pad57)") (class "Default")
      (node (ref "J1310") (pin "57") (pinfunction "57_57") (pintype "passive+no_connect"))
    )
    (net (code "164") (name "unconnected-(J1310-Pad59)") (class "Default")
      (node (ref "J1310") (pin "59") (pinfunction "59_59") (pintype "passive+no_connect"))
    )
    (net (code "165") (name "unconnected-(J1310-Pad61)") (class "Default")
      (node (ref "J1310") (pin "61") (pinfunction "61_61") (pintype "passive+no_connect"))
    )
    (net (code "166") (name "unconnected-(J1310-Pad81)") (class "Default")
      (node (ref "J1310") (pin "81") (pinfunction "81_81") (pintype "passive+no_connect"))
    )
    (net (code "167") (name "unconnected-(J1310-Pad82)") (class "Default")
      (node (ref "J1310") (pin "82") (pinfunction "82_82") (pintype "passive+no_connect"))
    )
    (net (code "168") (name "unconnected-(J1310-Pad89)") (class "Default")
      (node (ref "J1310") (pin "89") (pinfunction "89_89") (pintype "passive+no_connect"))
    )
    (net (code "169") (name "unconnected-(J1310-Pad92)") (class "Default")
      (node (ref "J1310") (pin "92") (pinfunction "92_92") (pintype "passive+no_connect"))
    )
    (net (code "170") (name "unconnected-(J1311-Pad3)") (class "Default")
      (node (ref "J1311") (pin "3") (pinfunction "3_3") (pintype "passive+no_connect"))
    )
    (net (code "171") (name "unconnected-(J1311-Pad5)") (class "Default")
      (node (ref "J1311") (pin "5") (pinfunction "5_5") (pintype "passive+no_connect"))
    )
    (net (code "172") (name "unconnected-(J1311-Pad9)") (class "Default")
      (node (ref "J1311") (pin "9") (pinfunction "9_9") (pintype "passive+no_connect"))
    )
    (net (code "173") (name "unconnected-(J1311-Pad11)") (class "Default")
      (node (ref "J1311") (pin "11") (pinfunction "11_11") (pintype "passive+no_connect"))
    )
    (net (code "174") (name "unconnected-(J1311-Pad15)") (class "Default")
      (node (ref "J1311") (pin "15") (pinfunction "15_15") (pintype "passive+no_connect"))
    )
    (net (code "175") (name "unconnected-(J1311-Pad17)") (class "Default")
      (node (ref "J1311") (pin "17") (pinfunction "17_17") (pintype "passive+no_connect"))
    )
    (net (code "176") (name "unconnected-(J1311-Pad22)") (class "Default")
      (node (ref "J1311") (pin "22") (pinfunction "22_22") (pintype "passive+no_connect"))
    )
    (net (code "177") (name "unconnected-(J1311-Pad24)") (class "Default")
      (node (ref "J1311") (pin "24") (pinfunction "24_24") (pintype "passive+no_connect"))
    )
    (net (code "178") (name "unconnected-(J1311-Pad28)") (class "Default")
      (node (ref "J1311") (pin "28") (pinfunction "28_28") (pintype "passive+no_connect"))
    )
    (net (code "179") (name "unconnected-(J1311-Pad30)") (class "Default")
      (node (ref "J1311") (pin "30") (pinfunction "30_30") (pintype "passive+no_connect"))
    )
    (net (code "180") (name "unconnected-(J1311-Pad33)") (class "Default")
      (node (ref "J1311") (pin "33") (pinfunction "33_33") (pintype "passive+no_connect"))
    )
    (net (code "181") (name "unconnected-(J1311-Pad34)") (class "Default")
      (node (ref "J1311") (pin "34") (pinfunction "34_34") (pintype "passive+no_connect"))
    )
    (net (code "182") (name "unconnected-(J1311-Pad35)") (class "Default")
      (node (ref "J1311") (pin "35") (pinfunction "35_35") (pintype "passive+no_connect"))
    )
    (net (code "183") (name "unconnected-(J1311-Pad36)") (class "Default")
      (node (ref "J1311") (pin "36") (pinfunction "36_36") (pintype "passive+no_connect"))
    )
    (net (code "184") (name "unconnected-(J1311-Pad39)") (class "Default")
      (node (ref "J1311") (pin "39") (pinfunction "39_39") (pintype "passive+no_connect"))
    )
    (net (code "185") (name "unconnected-(J1311-Pad41)") (class "Default")
      (node (ref "J1311") (pin "41") (pinfunction "41_41") (pintype "passive+no_connect"))
    )
    (net (code "186") (name "unconnected-(J1311-Pad78)") (class "Default")
      (node (ref "J1311") (pin "78") (pinfunction "78_78") (pintype "passive+no_connect"))
    )
    (net (code "187") (name "unconnected-(J1311-Pad88)") (class "Default")
      (node (ref "J1311") (pin "88") (pinfunction "88_88") (pintype "passive+no_connect"))
    )
    (net (code "188") (name "unconnected-(J1311-Pad92)") (class "Default")
      (node (ref "J1311") (pin "92") (pinfunction "92_92") (pintype "passive+no_connect"))
    )
    (net (code "189") (name "unconnected-(J1311-Pad96)") (class "Default")
      (node (ref "J1311") (pin "96") (pinfunction "96_96") (pintype "passive+no_connect"))
    )
    (net (code "190") (name "unconnected-(J1312-Pad6)") (class "Default")
      (node (ref "J1312") (pin "6") (pinfunction "6_6") (pintype "passive+no_connect"))
    )
    (net (code "191") (name "unconnected-(J1312-Pad13)") (class "Default")
      (node (ref "J1312") (pin "13") (pinfunction "13_13") (pintype "passive+no_connect"))
    )
    (net (code "192") (name "unconnected-(J1312-Pad15)") (class "Default")
      (node (ref "J1312") (pin "15") (pinfunction "15_15") (pintype "passive+no_connect"))
    )
    (net (code "193") (name "unconnected-(J1312-Pad17)") (class "Default")
      (node (ref "J1312") (pin "17") (pinfunction "17_17") (pintype "passive+no_connect"))
    )
    (net (code "194") (name "unconnected-(J1312-Pad19)") (class "Default")
      (node (ref "J1312") (pin "19") (pinfunction "19_19") (pintype "passive+no_connect"))
    )
    (net (code "195") (name "unconnected-(J1312-Pad21)") (class "Default")
      (node (ref "J1312") (pin "21") (pinfunction "21_21") (pintype "passive+no_connect"))
    )
    (net (code "196") (name "unconnected-(J1312-Pad23)") (class "Default")
      (node (ref "J1312") (pin "23") (pinfunction "23_23") (pintype "passive+no_connect"))
    )
    (net (code "197") (name "unconnected-(J1312-Pad25)") (class "Default")
      (node (ref "J1312") (pin "25") (pinfunction "25_25") (pintype "passive+no_connect"))
    )
    (net (code "198") (name "unconnected-(J1312-Pad26)") (class "Default")
      (node (ref "J1312") (pin "26") (pinfunction "26_26") (pintype "passive+no_connect"))
    )
    (net (code "199") (name "unconnected-(J1312-Pad27)") (class "Default")
      (node (ref "J1312") (pin "27") (pinfunction "27_27") (pintype "passive+no_connect"))
    )
    (net (code "200") (name "unconnected-(J1312-Pad29)") (class "Default")
      (node (ref "J1312") (pin "29") (pinfunction "29_29") (pintype "passive+no_connect"))
    )
    (net (code "201") (name "unconnected-(J1312-Pad31)") (class "Default")
      (node (ref "J1312") (pin "31") (pinfunction "31_31") (pintype "passive+no_connect"))
    )
    (net (code "202") (name "unconnected-(J1312-Pad35)") (class "Default")
      (node (ref "J1312") (pin "35") (pinfunction "35_35") (pintype "passive+no_connect"))
    )
    (net (code "203") (name "unconnected-(J1312-Pad36)") (class "Default")
      (node (ref "J1312") (pin "36") (pinfunction "36_36") (pintype "passive+no_connect"))
    )
    (net (code "204") (name "unconnected-(J1312-Pad37)") (class "Default")
      (node (ref "J1312") (pin "37") (pinfunction "37_37") (pintype "passive+no_connect"))
    )
    (net (code "205") (name "unconnected-(J1312-Pad41)") (class "Default")
      (node (ref "J1312") (pin "41") (pinfunction "41_41") (pintype "passive+no_connect"))
    )
    (net (code "206") (name "unconnected-(J1312-Pad42)") (class "Default")
      (node (ref "J1312") (pin "42") (pinfunction "42_42") (pintype "passive+no_connect"))
    )
    (net (code "207") (name "unconnected-(J1312-Pad67)") (class "Default")
      (node (ref "J1312") (pin "67") (pinfunction "67_67") (pintype "passive+no_connect"))
    )
    (net (code "208") (name "unconnected-(J1312-Pad69)") (class "Default")
      (node (ref "J1312") (pin "69") (pinfunction "69_69") (pintype "passive+no_connect"))
    )
  )
)
